# OSO-MISC-21-021_Sensor_Watch_Motion_II.net
KiCad netlist of a schematic drawn in EAGLE
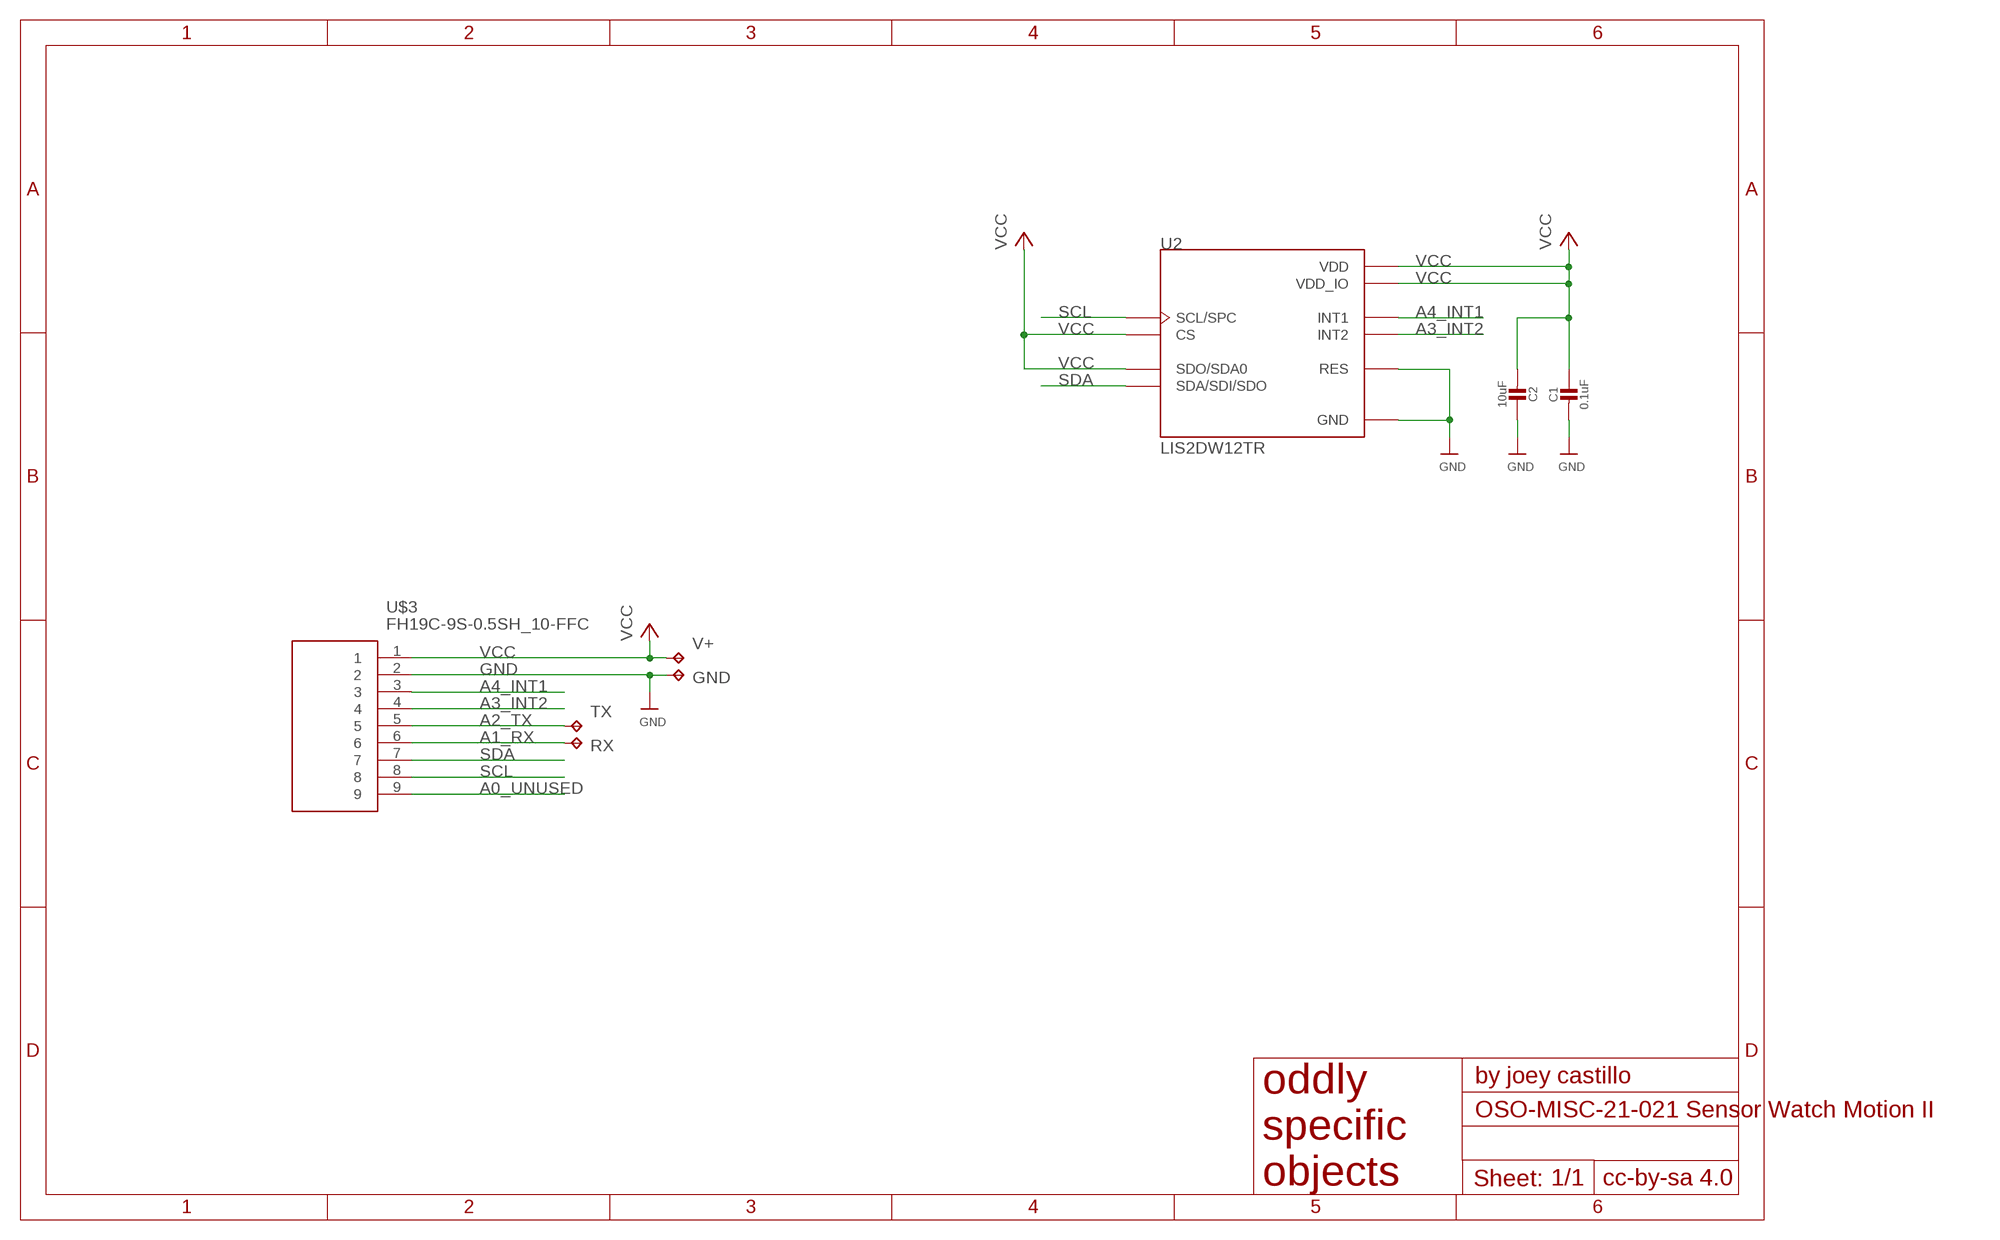
[diagram p0: schematic, sheet 1]

(export (version "E")
  (design (tool "Eeschema 10.0.6"))
  (components
    (comp (ref "C1")
      (value "0.1uF")
      (footprint "eagle-import:_0603MP")
      (libsource (lib "eagle-import") (part "CAP_CERAMIC_0603MP"))
    )
    (comp (ref "C2")
      (value "10uF")
      (footprint "eagle-import:_0603MP")
      (libsource (lib "eagle-import") (part "CAP_CERAMIC_0603MP"))
    )
    (comp (ref "GND")
      (value "TPB1,27")
      (footprint "eagle-import:B1,27")
      (libsource (lib "eagle-import") (part "TPB1,27"))
    )
    (comp (ref "RX")
      (value "TPB1,27")
      (footprint "eagle-import:B1,27")
      (libsource (lib "eagle-import") (part "TPB1,27"))
    )
    (comp (ref "TX")
      (value "TPB1,27")
      (footprint "eagle-import:B1,27")
      (libsource (lib "eagle-import") (part "TPB1,27"))
    )
    (comp (ref "U$3")
      (value "FH19C-9S-0.5SH_10-FFC")
      (footprint "eagle-import:FH19C9S05SH10-FFC")
      (libsource (lib "eagle-import") (part "FH19C-9S-0.5SH_10-FFC"))
    )
    (comp (ref "U2")
      (value "LIS2DW12TR")
      (footprint "eagle-import:LGA12R50P4X4_200X200X70")
      (fields (field (name "MF") "STMicroelectronics"))
      (libsource (lib "eagle-import") (part "LIS2DW12TR"))
    )
    (comp (ref "V+")
      (value "TPB1,27")
      (footprint "eagle-import:B1,27")
      (libsource (lib "eagle-import") (part "TPB1,27"))
    )
  )
  (nets
    (net (code "1") (name "/A0_UNUSED") (class "Default")
      (node (ref "U$3") (pin "9") (pinfunction "9_9") (pintype "bidirectional"))
    )
    (net (code "2") (name "/A1_RX") (class "Default")
      (node (ref "RX") (pin "TP") (pinfunction "TP_TP") (pintype "input"))
      (node (ref "U$3") (pin "6") (pinfunction "6_6") (pintype "bidirectional"))
    )
    (net (code "3") (name "/A2_TX") (class "Default")
      (node (ref "TX") (pin "TP") (pinfunction "TP_TP") (pintype "input"))
      (node (ref "U$3") (pin "5") (pinfunction "5_5") (pintype "bidirectional"))
    )
    (net (code "4") (name "/A3_INT2") (class "Default")
      (node (ref "U$3") (pin "4") (pinfunction "4_4") (pintype "bidirectional"))
      (node (ref "U2") (pin "11") (pinfunction "INT2_11") (pintype "output"))
    )
    (net (code "5") (name "/A4_INT1") (class "Default")
      (node (ref "U$3") (pin "3") (pinfunction "3_3") (pintype "bidirectional"))
      (node (ref "U2") (pin "12") (pinfunction "INT1_12") (pintype "output"))
    )
    (net (code "6") (name "/SCL") (class "Default")
      (node (ref "U$3") (pin "8") (pinfunction "8_8") (pintype "bidirectional"))
      (node (ref "U2") (pin "1") (pinfunction "SCL/SPC_1") (pintype "input"))
    )
    (net (code "7") (name "/SDA") (class "Default")
      (node (ref "U$3") (pin "7") (pinfunction "7_7") (pintype "bidirectional"))
      (node (ref "U2") (pin "4") (pinfunction "SDA/SDI/SDO_4") (pintype "bidirectional"))
    )
    (net (code "8") (name "GND") (class "Default")
      (node (ref "C1") (pin "2") (pinfunction "2_2") (pintype "passive"))
      (node (ref "C2") (pin "1") (pinfunction "1_1") (pintype "passive"))
      (node (ref "GND") (pin "TP") (pinfunction "TP_TP") (pintype "input"))
      (node (ref "U$3") (pin "2") (pinfunction "2_2") (pintype "bidirectional"))
      (node (ref "U2") (pin "6") (pinfunction "GND_6") (pintype "power_in"))
      (node (ref "U2") (pin "7") (pinfunction "RES_7") (pintype "passive"))
      (node (ref "U2") (pin "8") (pinfunction "GND_8") (pintype "power_in"))
    )
    (net (code "9") (name "VCC") (class "Default")
      (node (ref "C1") (pin "1") (pinfunction "1_1") (pintype "passive"))
      (node (ref "C2") (pin "2") (pinfunction "2_2") (pintype "passive"))
      (node (ref "U$3") (pin "1") (pinfunction "1_1") (pintype "bidirectional"))
      (node (ref "U2") (pin "10") (pinfunction "VDD_IO_10") (pintype "power_in"))
      (node (ref "U2") (pin "2") (pinfunction "CS_2") (pintype "input"))
      (node (ref "U2") (pin "3") (pinfunction "SDO/SDA0_3") (pintype "bidirectional"))
      (node (ref "U2") (pin "9") (pinfunction "VDD_9") (pintype "power_in"))
      (node (ref "V+") (pin "TP") (pinfunction "TP_TP") (pintype "input"))
    )
  )
)
